# sch.net
KiCad netlist of a schematic drawn in Altium Designer
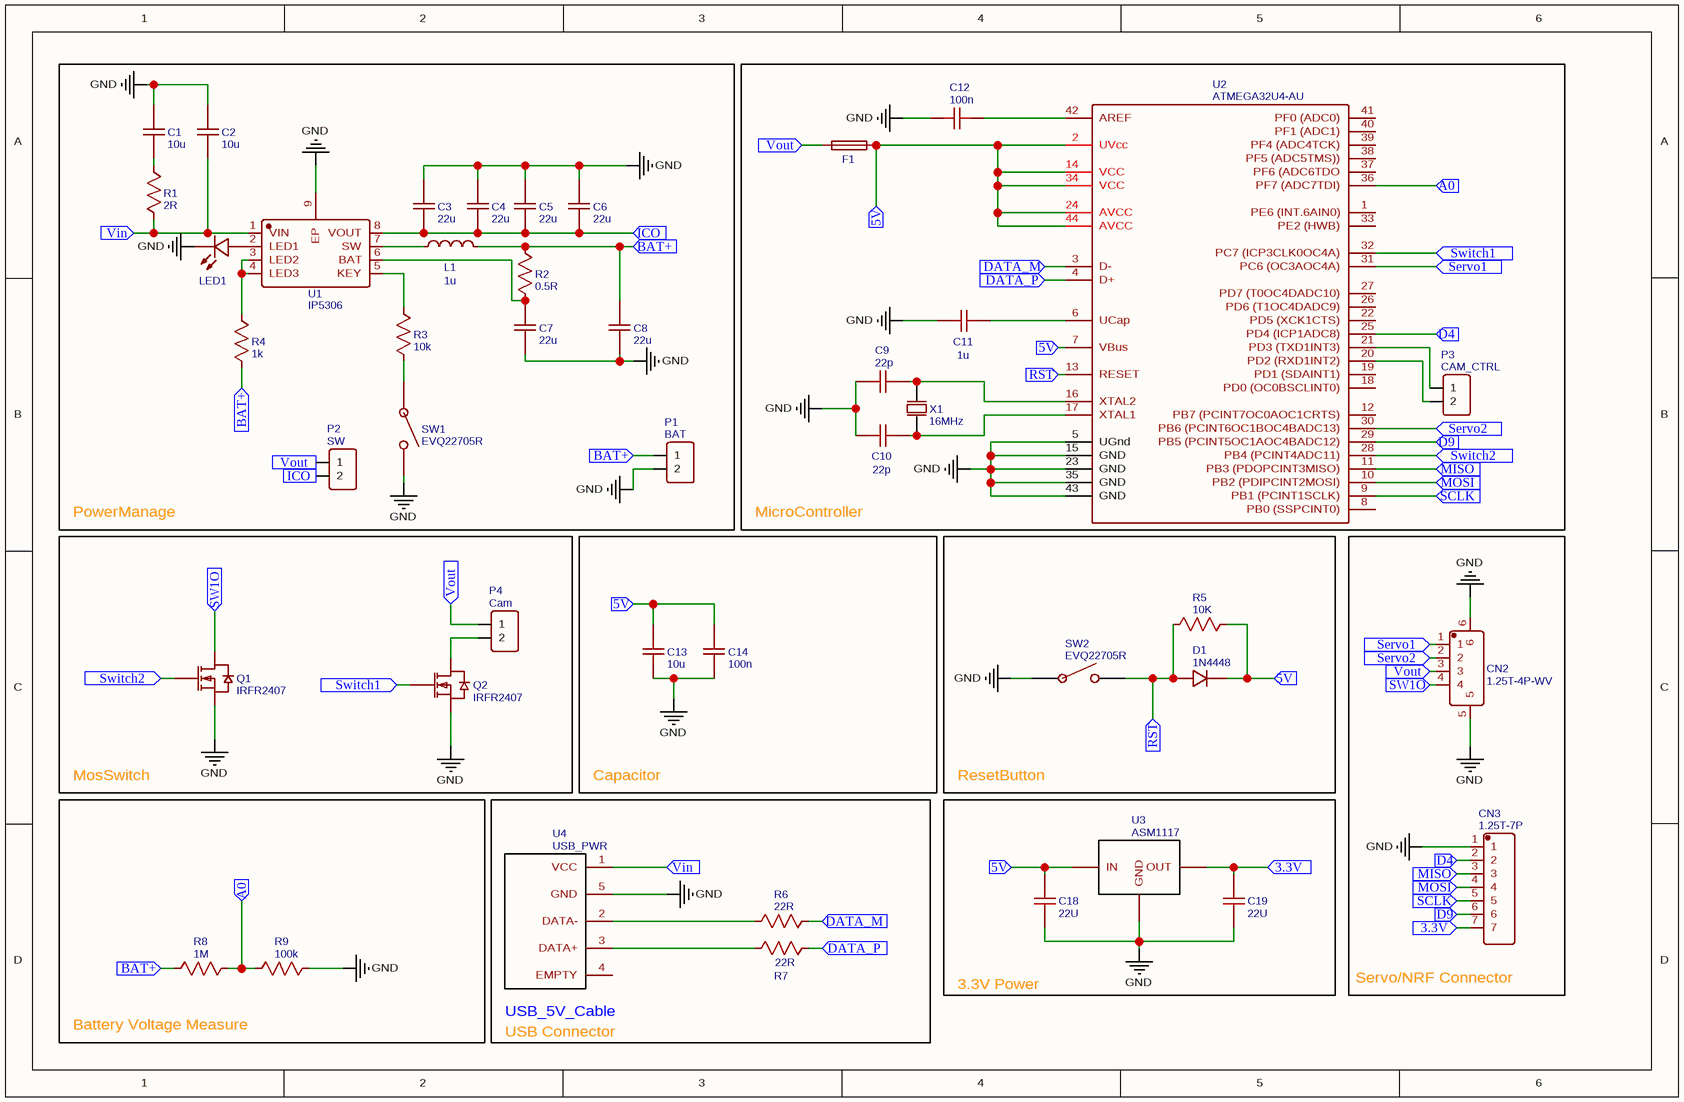
[diagram p0: sch.schdoc]

(export (version "E")
  (design (tool "Eeschema 10.0.6"))
  (components
    (comp (ref "C1") (value "10u") (libsource (lib "altium-import") (part "root_0_10u_")))
    (comp (ref "C2") (value "10u") (libsource (lib "altium-import") (part "root_0_10u_")))
    (comp (ref "C3") (value "22u") (libsource (lib "altium-import") (part "root_0_22u_")))
    (comp (ref "C4") (value "22u") (libsource (lib "altium-import") (part "root_0_22u_")))
    (comp (ref "C5") (value "22u") (libsource (lib "altium-import") (part "root_0_22u_")))
    (comp (ref "C6") (value "22u") (libsource (lib "altium-import") (part "root_0_22u_")))
    (comp (ref "C7") (value "22u") (libsource (lib "altium-import") (part "root_0_22u_")))
    (comp (ref "C8") (value "22u") (libsource (lib "altium-import") (part "root_0_22u_")))
    (comp (ref "C9") (value "22p") (libsource (lib "altium-import") (part "root_3_22p_")))
    (comp (ref "C10") (value "22p") (libsource (lib "altium-import") (part "root_3_22p_")))
    (comp (ref "C11") (value "1u") (libsource (lib "altium-import") (part "root_1_1u_")))
    (comp (ref "C12") (value "100n") (libsource (lib "altium-import") (part "root_1_100n_")))
    (comp (ref "C13") (value "10u") (libsource (lib "altium-import") (part "root_0_10u_")))
    (comp (ref "C14") (value "100n") (libsource (lib "altium-import") (part "root_0_100n_")))
    (comp (ref "C18") (value "22U") (libsource (lib "altium-import") (part "root_0_22U_")))
    (comp (ref "C19") (value "22U") (libsource (lib "altium-import") (part "root_0_22U_")))
    (comp (ref "CN2")
      (value "1.25T-4P-WV")
      (fields (field (name "BOM_SUPPLIER PART") "C145934") (field (name "CONTRIBUTOR") "LCSC"))
      (libsource (lib "altium-import") (part "root_0_1.25T-4P-WV_"))
    )
    (comp (ref "CN3")
      (value "1.25T-7P")
      (fields (field (name "BOM_SUPPLIER PART") "C51274"))
      (libsource (lib "altium-import") (part "root_0_1.25T-7P_"))
    )
    (comp (ref "D1")
      (value "1N4448")
      (fields (field (name "BOM_SUPPLIER PART") "C54037"))
      (libsource (lib "altium-import") (part "root_0_1N4448_"))
    )
    (comp (ref "F1")
      (value "Glass tube fuse2A 3F 250VAC")
      (fields (field (name "BOM_SUPPLIER PART") "C71017"))
      (libsource (lib "altium-import") (part "root_0_Glass tube fuse2A 3F 250VAC_"))
    )
    (comp (ref "L1") (value "1u") (libsource (lib "altium-import") (part "root_0_1u_")))
    (comp (ref "LED1")
      (value "LTST-C170TBKT")
      (fields (field (name "BOM_SUPPLIER PART") "C98222") (field (name "CONTRIBUTOR") "LCSC"))
      (libsource (lib "altium-import") (part "root_2_LTST-C170TBKT_"))
    )
    (comp (ref "P1")
      (value "BAT")
      (fields
        (field (name "BOM_MANUFACTURER PART") "2.54-1*2PFemale")
        (field (name "BOM_SUPPLIER PART") "C49661")
      )
      (libsource (lib "altium-import") (part "root_0_BAT_"))
    )
    (comp (ref "P2")
      (value "SW")
      (fields
        (field (name "BOM_MANUFACTURER PART") "2.54-1*2PFemale")
        (field (name "BOM_SUPPLIER PART") "C49661")
      )
      (libsource (lib "altium-import") (part "root_0_SW_"))
    )
    (comp (ref "P3")
      (value "CAM_CTRL")
      (fields
        (field (name "BOM_MANUFACTURER PART") "2.54-1*2PFemale")
        (field (name "BOM_SUPPLIER PART") "C49661")
      )
      (libsource (lib "altium-import") (part "root_0_CAM_CTRL_"))
    )
    (comp (ref "P4")
      (value "Cam")
      (fields
        (field (name "BOM_MANUFACTURER PART") "2.54-1*2PFemale")
        (field (name "BOM_SUPPLIER PART") "C49661")
      )
      (libsource (lib "altium-import") (part "root_0_Cam_"))
    )
    (comp (ref "Q1")
      (value "IRFR2407")
      (fields (field (name "BOM_SUPPLIER PART") "C40514"))
      (libsource (lib "altium-import") (part "root_0_IRFR2407_"))
    )
    (comp (ref "Q2")
      (value "IRFR2407")
      (fields (field (name "BOM_SUPPLIER PART") "C40514"))
      (libsource (lib "altium-import") (part "root_0_IRFR2407_"))
    )
    (comp (ref "R1") (value "2R") (libsource (lib "altium-import") (part "root_1_2R_")))
    (comp (ref "R2") (value "0.5R") (libsource (lib "altium-import") (part "root_1_0.5R_")))
    (comp (ref "R3") (value "10k") (libsource (lib "altium-import") (part "root_1_10k_")))
    (comp (ref "R4") (value "1k") (libsource (lib "altium-import") (part "root_1_1k_")))
    (comp (ref "R5") (value "10K") (libsource (lib "altium-import") (part "root_0_10K_")))
    (comp (ref "R6") (value "22R") (libsource (lib "altium-import") (part "root_0_22R_")))
    (comp (ref "R7") (value "22R") (libsource (lib "altium-import") (part "root_0_22R_")))
    (comp (ref "R8") (value "1M") (libsource (lib "altium-import") (part "root_0_1M_")))
    (comp (ref "R9") (value "100k") (libsource (lib "altium-import") (part "root_0_100k_")))
    (comp (ref "SW1")
      (value "EVQ22705R")
      (fields (field (name "BOM_SUPPLIER PART") "C79156") (field (name "CONTRIBUTOR") "LCSC"))
      (libsource (lib "altium-import") (part "root_3_EVQ22705R_"))
    )
    (comp (ref "SW2")
      (value "EVQ22705R")
      (fields (field (name "BOM_SUPPLIER PART") "C79156") (field (name "CONTRIBUTOR") "LCSC"))
      (libsource (lib "altium-import") (part "root_0_EVQ22705R_"))
    )
    (comp (ref "U1")
      (value "IP5306")
      (fields (field (name "BOM_SUPPLIER PART") "C181692") (field (name "CONTRIBUTOR") "LCSC"))
      (libsource (lib "altium-import") (part "root_0_IP5306_"))
    )
    (comp (ref "U2")
      (value "ATMEGA32U4-AU")
      (fields (field (name "BOM_SUPPLIER PART") "C44854"))
      (libsource (lib "altium-import") (part "root_0_ATMEGA32U4-AU_"))
    )
    (comp (ref "U3")
      (value "ASM1117")
      (fields (field (name "CONTRIBUTOR") "xsu"))
      (libsource (lib "altium-import") (part "root_0_ASM1117_"))
    )
    (comp (ref "U4")
      (value "USB_PWR")
      (fields (field (name "CONTRIBUTOR") "Dimsmary"))
      (libsource (lib "altium-import") (part "root_0_USB_PWR_"))
    )
    (comp (ref "X1")
      (value "16MHz")
      (fields
        (field (name "BOM_MANUFACTURER PART") "E49A16E00000KE10CO")
        (field (name "BOM_SUPPLIER PART") "C114981")
      )
      (libsource (lib "altium-import") (part "root_1_16MHz_"))
    )
  )
  (nets
    (net (code "1") (name "/3.3V") (class "Default")
      (node (ref "C19") (pin "2") (pinfunction "2_2") (pintype "passive"))
      (node (ref "CN3") (pin "7") (pinfunction "7_7") (pintype "passive"))
      (node (ref "U3") (pin "2") (pinfunction "OUT_2") (pintype "passive"))
    )
    (net (code "2") (name "/5V") (class "Default")
      (node (ref "C13") (pin "2") (pinfunction "2_2") (pintype "passive"))
      (node (ref "C14") (pin "2") (pinfunction "2_2") (pintype "passive"))
      (node (ref "C18") (pin "2") (pinfunction "2_2") (pintype "passive"))
      (node (ref "D1") (pin "2") (pinfunction "K_2") (pintype "passive"))
      (node (ref "F1") (pin "2") (pinfunction "2_2") (pintype "passive"))
      (node (ref "R5") (pin "2") (pinfunction "2_2") (pintype "passive"))
      (node (ref "U2") (pin "14") (pinfunction "VCC_14") (pintype "passive"))
      (node (ref "U2") (pin "2") (pinfunction "UVcc_2") (pintype "passive"))
      (node (ref "U2") (pin "24") (pinfunction "AVCC_24") (pintype "passive"))
      (node (ref "U2") (pin "34") (pinfunction "VCC_34") (pintype "passive"))
      (node (ref "U2") (pin "44") (pinfunction "AVCC_44") (pintype "passive"))
      (node (ref "U2") (pin "7") (pinfunction "VBus_7") (pintype "passive"))
      (node (ref "U3") (pin "3") (pinfunction "IN_3") (pintype "passive"))
    )
    (net (code "3") (name "/A0") (class "Default")
      (node (ref "R8") (pin "2") (pinfunction "2_2") (pintype "passive"))
      (node (ref "R9") (pin "1") (pinfunction "1_1") (pintype "passive"))
      (node (ref "U2") (pin "36") (pinfunction "PF7_(ADC7TDI)_36") (pintype "passive"))
    )
    (net (code "4") (name "/BAT+") (class "Default")
      (node (ref "C8") (pin "2") (pinfunction "2_2") (pintype "passive"))
      (node (ref "L1") (pin "2") (pinfunction "2_2") (pintype "passive"))
      (node (ref "P1") (pin "1") (pinfunction "1_1") (pintype "passive"))
      (node (ref "R2") (pin "2") (pinfunction "2_2") (pintype "passive"))
      (node (ref "R4") (pin "1") (pinfunction "1_1") (pintype "passive"))
      (node (ref "R8") (pin "1") (pinfunction "1_1") (pintype "passive"))
    )
    (net (code "5") (name "/D4") (class "Default")
      (node (ref "CN3") (pin "2") (pinfunction "2_2") (pintype "passive"))
      (node (ref "U2") (pin "25") (pinfunction "PD4_(ICP1ADC8)_25") (pintype "passive"))
    )
    (net (code "6") (name "/D9") (class "Default")
      (node (ref "CN3") (pin "6") (pinfunction "6_6") (pintype "passive"))
      (node (ref "U2") (pin "29") (pinfunction "PB5_(PCINT5OC1AOC4BADC12)_29") (pintype "passive"))
    )
    (net (code "7") (name "/DATA_M") (class "Default")
      (node (ref "R6") (pin "2") (pinfunction "2_2") (pintype "passive"))
      (node (ref "U2") (pin "3") (pinfunction "D-_3") (pintype "passive"))
    )
    (net (code "8") (name "/DATA_P") (class "Default")
      (node (ref "R7") (pin "2") (pinfunction "2_2") (pintype "passive"))
      (node (ref "U2") (pin "4") (pinfunction "D+_4") (pintype "passive"))
    )
    (net (code "9") (name "/ICO") (class "Default")
      (node (ref "C3") (pin "1") (pinfunction "1_1") (pintype "passive"))
      (node (ref "C4") (pin "1") (pinfunction "1_1") (pintype "passive"))
      (node (ref "C5") (pin "1") (pinfunction "1_1") (pintype "passive"))
      (node (ref "C6") (pin "1") (pinfunction "1_1") (pintype "passive"))
      (node (ref "P2") (pin "2") (pinfunction "2_2") (pintype "passive"))
      (node (ref "U1") (pin "8") (pinfunction "VOUT_8") (pintype "passive"))
    )
    (net (code "10") (name "/MISO") (class "Default")
      (node (ref "CN3") (pin "3") (pinfunction "3_3") (pintype "passive"))
      (node (ref "U2") (pin "11") (pinfunction "PB3_(PDOPCINT3MISO)_11") (pintype "passive"))
    )
    (net (code "11") (name "/MOSI") (class "Default")
      (node (ref "CN3") (pin "4") (pinfunction "4_4") (pintype "passive"))
      (node (ref "U2") (pin "10") (pinfunction "PB2_(PDIPCINT2MOSI)_10") (pintype "passive"))
    )
    (net (code "12") (name "/RST") (class "Default")
      (node (ref "D1") (pin "1") (pinfunction "A_1") (pintype "passive"))
      (node (ref "R5") (pin "1") (pinfunction "1_1") (pintype "passive"))
      (node (ref "SW2") (pin "2") (pinfunction "2_2") (pintype "passive"))
      (node (ref "U2") (pin "13") (pinfunction "RESET_13") (pintype "passive"))
    )
    (net (code "13") (name "/SCLK") (class "Default")
      (node (ref "CN3") (pin "5") (pinfunction "5_5") (pintype "passive"))
      (node (ref "U2") (pin "9") (pinfunction "PB1_(PCINT1SCLK)_9") (pintype "passive"))
    )
    (net (code "14") (name "/SW1O") (class "Default")
      (node (ref "CN2") (pin "4") (pinfunction "4_4") (pintype "passive"))
      (node (ref "Q1") (pin "2") (pinfunction "D_2") (pintype "passive"))
    )
    (net (code "15") (name "/Servo1") (class "Default")
      (node (ref "CN2") (pin "1") (pinfunction "1_1") (pintype "passive"))
      (node (ref "U2") (pin "31") (pinfunction "PC6_(OC3AOC4A)_31") (pintype "passive"))
    )
    (net (code "16") (name "/Servo2") (class "Default")
      (node (ref "CN2") (pin "2") (pinfunction "2_2") (pintype "passive"))
      (node (ref "U2") (pin "30") (pinfunction "PB6_(PCINT6OC1BOC4BADC13)_30") (pintype "passive"))
    )
    (net (code "17") (name "/Switch1") (class "Default")
      (node (ref "Q2") (pin "1") (pinfunction "G_1") (pintype "passive"))
      (node (ref "U2") (pin "32") (pinfunction "PC7_(ICP3CLK0OC4A)_32") (pintype "passive"))
    )
    (net (code "18") (name "/Switch2") (class "Default")
      (node (ref "Q1") (pin "1") (pinfunction "G_1") (pintype "passive"))
      (node (ref "U2") (pin "28") (pinfunction "PB4_(PCINT4ADC11)_28") (pintype "passive"))
    )
    (net (code "19") (name "/Vin") (class "Default")
      (node (ref "C2") (pin "1") (pinfunction "1_1") (pintype "passive"))
      (node (ref "R1") (pin "1") (pinfunction "1_1") (pintype "passive"))
      (node (ref "U1") (pin "1") (pinfunction "VIN_1") (pintype "passive"))
      (node (ref "U4") (pin "1") (pinfunction "VCC_1") (pintype "passive"))
    )
    (net (code "20") (name "/Vout") (class "Default")
      (node (ref "CN2") (pin "3") (pinfunction "3_3") (pintype "passive"))
      (node (ref "F1") (pin "1") (pinfunction "1_1") (pintype "passive"))
      (node (ref "P2") (pin "1") (pinfunction "1_1") (pintype "passive"))
      (node (ref "P4") (pin "1") (pinfunction "1_1") (pintype "passive"))
    )
    (net (code "21") (name "GND") (class "Default")
      (node (ref "C1") (pin "2") (pinfunction "2_2") (pintype "passive"))
      (node (ref "C10") (pin "1") (pinfunction "1_1") (pintype "passive"))
      (node (ref "C11") (pin "2") (pinfunction "2_2") (pintype "passive"))
      (node (ref "C12") (pin "2") (pinfunction "2_2") (pintype "passive"))
      (node (ref "C13") (pin "1") (pinfunction "1_1") (pintype "passive"))
      (node (ref "C14") (pin "1") (pinfunction "1_1") (pintype "passive"))
      (node (ref "C18") (pin "1") (pinfunction "1_1") (pintype "passive"))
      (node (ref "C19") (pin "1") (pinfunction "1_1") (pintype "passive"))
      (node (ref "C2") (pin "2") (pinfunction "2_2") (pintype "passive"))
      (node (ref "C3") (pin "2") (pinfunction "2_2") (pintype "passive"))
      (node (ref "C4") (pin "2") (pinfunction "2_2") (pintype "passive"))
      (node (ref "C5") (pin "2") (pinfunction "2_2") (pintype "passive"))
      (node (ref "C6") (pin "2") (pinfunction "2_2") (pintype "passive"))
      (node (ref "C7") (pin "1") (pinfunction "1_1") (pintype "passive"))
      (node (ref "C8") (pin "1") (pinfunction "1_1") (pintype "passive"))
      (node (ref "C9") (pin "1") (pinfunction "1_1") (pintype "passive"))
      (node (ref "CN2") (pin "5") (pinfunction "5_5") (pintype "passive"))
      (node (ref "CN2") (pin "6") (pinfunction "6_6") (pintype "passive"))
      (node (ref "CN3") (pin "1") (pinfunction "1_1") (pintype "passive"))
      (node (ref "LED1") (pin "2") (pinfunction "K_2") (pintype "passive"))
      (node (ref "P1") (pin "2") (pinfunction "2_2") (pintype "passive"))
      (node (ref "Q1") (pin "3") (pinfunction "S_3") (pintype "passive"))
      (node (ref "Q2") (pin "3") (pinfunction "S_3") (pintype "passive"))
      (node (ref "R9") (pin "2") (pinfunction "2_2") (pintype "passive"))
      (node (ref "SW1") (pin "2") (pinfunction "2_2") (pintype "passive"))
      (node (ref "SW2") (pin "1") (pinfunction "1_1") (pintype "passive"))
      (node (ref "U1") (pin "9") (pinfunction "EP_9") (pintype "passive"))
      (node (ref "U2") (pin "15") (pinfunction "GND_15") (pintype "passive"))
      (node (ref "U2") (pin "23") (pinfunction "GND_23") (pintype "passive"))
      (node (ref "U2") (pin "35") (pinfunction "GND_35") (pintype "passive"))
      (node (ref "U2") (pin "43") (pinfunction "GND_43") (pintype "passive"))
      (node (ref "U2") (pin "5") (pinfunction "UGnd_5") (pintype "passive"))
      (node (ref "U3") (pin "1") (pinfunction "GND_1") (pintype "passive"))
      (node (ref "U4") (pin "5") (pinfunction "GND_5") (pintype "passive"))
    )
    (net (code "22") (name "Net-(C1-Pad1)") (class "Default")
      (node (ref "C1") (pin "1") (pinfunction "1_1") (pintype "passive"))
      (node (ref "R1") (pin "2") (pinfunction "2_2") (pintype "passive"))
    )
    (net (code "23") (name "Net-(LED1-A)") (class "Default")
      (node (ref "LED1") (pin "1") (pinfunction "A_1") (pintype "passive"))
      (node (ref "U1") (pin "2") (pinfunction "LED1_2") (pintype "passive"))
    )
    (net (code "24") (name "Net-(Q2-D)") (class "Default")
      (node (ref "P4") (pin "2") (pinfunction "2_2") (pintype "passive"))
      (node (ref "Q2") (pin "2") (pinfunction "D_2") (pintype "passive"))
    )
    (net (code "25") (name "Net-(R3-Pad1)") (class "Default")
      (node (ref "R3") (pin "1") (pinfunction "1_1") (pintype "passive"))
      (node (ref "SW1") (pin "1") (pinfunction "1_1") (pintype "passive"))
    )
    (net (code "26") (name "Net-(U1-BAT)") (class "Default")
      (node (ref "C7") (pin "2") (pinfunction "2_2") (pintype "passive"))
      (node (ref "R2") (pin "1") (pinfunction "1_1") (pintype "passive"))
      (node (ref "U1") (pin "6") (pinfunction "BAT_6") (pintype "passive"))
    )
    (net (code "27") (name "Net-(U1-KEY)") (class "Default")
      (node (ref "R3") (pin "2") (pinfunction "2_2") (pintype "passive"))
      (node (ref "U1") (pin "5") (pinfunction "KEY_5") (pintype "passive"))
    )
    (net (code "28") (name "Net-(U1-LED2)") (class "Default")
      (node (ref "R4") (pin "2") (pinfunction "2_2") (pintype "passive"))
      (node (ref "U1") (pin "3") (pinfunction "LED2_3") (pintype "passive"))
      (node (ref "U1") (pin "4") (pinfunction "LED3_4") (pintype "passive"))
    )
    (net (code "29") (name "Net-(U1-SW)") (class "Default")
      (node (ref "L1") (pin "1") (pinfunction "1_1") (pintype "passive"))
      (node (ref "U1") (pin "7") (pinfunction "SW_7") (pintype "passive"))
    )
    (net (code "30") (name "Net-(U2-AREF)") (class "Default")
      (node (ref "C12") (pin "1") (pinfunction "1_1") (pintype "passive"))
      (node (ref "U2") (pin "42") (pinfunction "AREF_42") (pintype "passive"))
    )
    (net (code "31") (name "Net-(U2-PD2_(RXD1INT2))") (class "Default")
      (node (ref "P3") (pin "2") (pinfunction "2_2") (pintype "passive"))
      (node (ref "U2") (pin "20") (pinfunction "PD2_(RXD1INT2)_20") (pintype "passive"))
    )
    (net (code "32") (name "Net-(U2-PD3_(TXD1INT3))") (class "Default")
      (node (ref "P3") (pin "1") (pinfunction "1_1") (pintype "passive"))
      (node (ref "U2") (pin "21") (pinfunction "PD3_(TXD1INT3)_21") (pintype "passive"))
    )
    (net (code "33") (name "Net-(U2-UCap)") (class "Default")
      (node (ref "C11") (pin "1") (pinfunction "1_1") (pintype "passive"))
      (node (ref "U2") (pin "6") (pinfunction "UCap_6") (pintype "passive"))
    )
    (net (code "34") (name "Net-(U2-XTAL1)") (class "Default")
      (node (ref "C10") (pin "2") (pinfunction "2_2") (pintype "passive"))
      (node (ref "U2") (pin "17") (pinfunction "XTAL1_17") (pintype "passive"))
      (node (ref "X1") (pin "2") (pinfunction "OSC2_2") (pintype "passive"))
    )
    (net (code "35") (name "Net-(U2-XTAL2)") (class "Default")
      (node (ref "C9") (pin "2") (pinfunction "2_2") (pintype "passive"))
      (node (ref "U2") (pin "16") (pinfunction "XTAL2_16") (pintype "passive"))
      (node (ref "X1") (pin "1") (pinfunction "OSC1_1") (pintype "passive"))
    )
    (net (code "36") (name "Net-(U4-DATA+)") (class "Default")
      (node (ref "R7") (pin "1") (pinfunction "1_1") (pintype "passive"))
      (node (ref "U4") (pin "3") (pinfunction "DATA+_3") (pintype "passive"))
    )
    (net (code "37") (name "Net-(U4-DATA-)") (class "Default")
      (node (ref "R6") (pin "1") (pinfunction "1_1") (pintype "passive"))
      (node (ref "U4") (pin "2") (pinfunction "DATA-_2") (pintype "passive"))
    )
    (net (code "38") (name "unconnected-(U2-PB0_(SSPCINT0)-Pad8)") (class "Default")
      (node (ref "U2") (pin "8") (pinfunction "PB0_(SSPCINT0)_8") (pintype "passive"))
    )
    (net (code "39") (name "unconnected-(U2-PB7_(PCINT7OC0AOC1CRTS)-Pad12)") (class "Default")
      (node (ref "U2") (pin "12") (pinfunction "PB7_(PCINT7OC0AOC1CRTS)_12") (pintype "passive"))
    )
    (net (code "40") (name "unconnected-(U2-PD0_(OC0BSCLINT0)-Pad18)") (class "Default")
      (node (ref "U2") (pin "18") (pinfunction "PD0_(OC0BSCLINT0)_18") (pintype "passive"))
    )
    (net (code "41") (name "unconnected-(U2-PD1_(SDAINT1)-Pad19)") (class "Default")
      (node (ref "U2") (pin "19") (pinfunction "PD1_(SDAINT1)_19") (pintype "passive"))
    )
    (net (code "42") (name "unconnected-(U2-PD5_(XCK1CTS)-Pad22)") (class "Default")
      (node (ref "U2") (pin "22") (pinfunction "PD5_(XCK1CTS)_22") (pintype "passive"))
    )
    (net (code "43") (name "unconnected-(U2-PD6_(T1OC4DADC9)-Pad26)") (class "Default")
      (node (ref "U2") (pin "26") (pinfunction "PD6_(T1OC4DADC9)_26") (pintype "passive"))
    )
    (net (code "44") (name "unconnected-(U2-PD7_(T0OC4DADC10)-Pad27)") (class "Default")
      (node (ref "U2") (pin "27") (pinfunction "PD7_(T0OC4DADC10)_27") (pintype "passive"))
    )
    (net (code "45") (name "unconnected-(U2-PE2_(HWB)-Pad33)") (class "Default")
      (node (ref "U2") (pin "33") (pinfunction "PE2_(HWB)_33") (pintype "passive"))
    )
    (net (code "46") (name "unconnected-(U2-PE6_(INT.6AIN0)-Pad1)") (class "Default")
      (node (ref "U2") (pin "1") (pinfunction "PE6_(INT.6AIN0)_1") (pintype "passive"))
    )
    (net (code "47") (name "unconnected-(U2-PF0_(ADC0)-Pad41)") (class "Default")
      (node (ref "U2") (pin "41") (pinfunction "PF0_(ADC0)_41") (pintype "passive"))
    )
    (net (code "48") (name "unconnected-(U2-PF1_(ADC1)-Pad40)") (class "Default")
      (node (ref "U2") (pin "40") (pinfunction "PF1_(ADC1)_40") (pintype "passive"))
    )
    (net (code "49") (name "unconnected-(U2-PF4_(ADC4TCK)-Pad39)") (class "Default")
      (node (ref "U2") (pin "39") (pinfunction "PF4_(ADC4TCK)_39") (pintype "passive"))
    )
    (net (code "50") (name "unconnected-(U2-PF5_(ADC5TMS))-Pad38)") (class "Default")
      (node (ref "U2") (pin "38") (pinfunction "PF5_(ADC5TMS))_38") (pintype "passive"))
    )
    (net (code "51") (name "unconnected-(U2-PF6_(ADC6TDO-Pad37)") (class "Default")
      (node (ref "U2") (pin "37") (pinfunction "PF6_(ADC6TDO_37") (pintype "passive"))
    )
    (net (code "52") (name "unconnected-(U4-EMPTY-Pad4)") (class "Default")
      (node (ref "U4") (pin "4") (pinfunction "EMPTY_4") (pintype "passive"))
    )
  )
)
